# perfboard.net
KiCad netlist of a schematic drawn in EAGLE
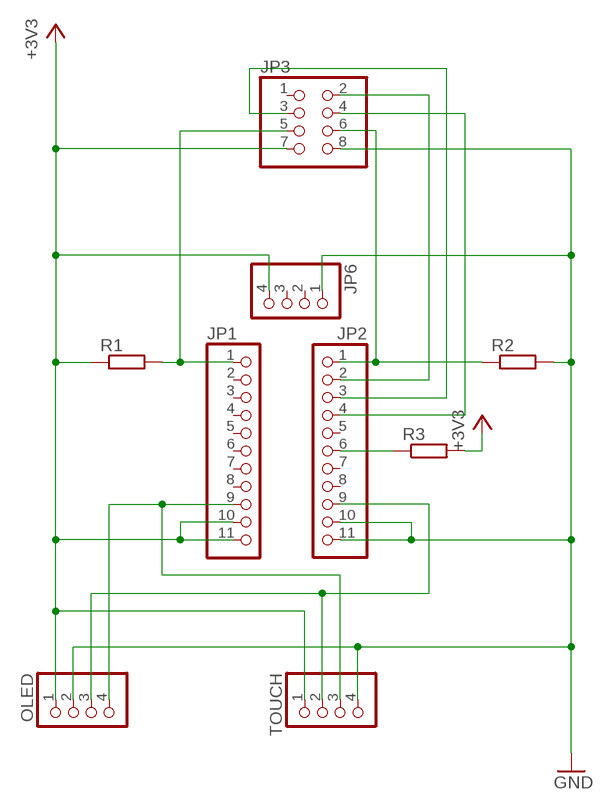
[diagram p0: schematic, sheet 1]

(export (version "E")
  (design (tool "Eeschema 10.0.6"))
  (components
    (comp (ref "JP1")
      (value "PINHD-1X11")
      (footprint "eagle-import:1X11")
      (libsource (lib "eagle-import") (part "PINHD-1X11"))
    )
    (comp (ref "JP2")
      (value "PINHD-1X11")
      (footprint "eagle-import:1X11")
      (libsource (lib "eagle-import") (part "PINHD-1X11"))
    )
    (comp (ref "JP3")
      (value "PINHD-2X4")
      (footprint "eagle-import:2X04")
      (libsource (lib "eagle-import") (part "PINHD-2X4"))
    )
    (comp (ref "JP6")
      (value "PINHD-1X4")
      (footprint "eagle-import:1X04")
      (libsource (lib "eagle-import") (part "PINHD-1X4"))
    )
    (comp (ref "OLED")
      (value "PINHD-1X4")
      (footprint "eagle-import:1X04")
      (libsource (lib "eagle-import") (part "PINHD-1X4"))
    )
    (comp (ref "R1")
      (value "R-EU_0207/7")
      (footprint "eagle-import:0207_7")
      (libsource (lib "eagle-import") (part "R-EU_0207/7"))
    )
    (comp (ref "R2")
      (value "R-EU_0207/7")
      (footprint "eagle-import:0207_7")
      (libsource (lib "eagle-import") (part "R-EU_0207/7"))
    )
    (comp (ref "R3")
      (value "R-EU_0207/7")
      (footprint "eagle-import:0207_7")
      (libsource (lib "eagle-import") (part "R-EU_0207/7"))
    )
    (comp (ref "TOUCH")
      (value "PINHD-1X4")
      (footprint "eagle-import:1X04")
      (libsource (lib "eagle-import") (part "PINHD-1X4"))
    )
  )
  (nets
    (net (code "1") (name "+3V3") (class "Default")
      (node (ref "JP1") (pin "10") (pinfunction "10_10") (pintype "passive"))
      (node (ref "JP1") (pin "11") (pinfunction "11_11") (pintype "passive"))
      (node (ref "JP3") (pin "7") (pinfunction "7_7") (pintype "passive"))
      (node (ref "JP6") (pin "4") (pinfunction "4_4") (pintype "passive"))
      (node (ref "OLED") (pin "1") (pinfunction "1_1") (pintype "passive"))
      (node (ref "R1") (pin "1") (pinfunction "1_1") (pintype "passive"))
      (node (ref "R3") (pin "2") (pinfunction "2_2") (pintype "passive"))
      (node (ref "TOUCH") (pin "1") (pinfunction "1_1") (pintype "passive"))
    )
    (net (code "2") (name "GND") (class "Default")
      (node (ref "JP2") (pin "10") (pinfunction "10_10") (pintype "passive"))
      (node (ref "JP2") (pin "11") (pinfunction "11_11") (pintype "passive"))
      (node (ref "JP3") (pin "8") (pinfunction "8_8") (pintype "passive"))
      (node (ref "JP6") (pin "1") (pinfunction "1_1") (pintype "passive"))
      (node (ref "OLED") (pin "2") (pinfunction "2_2") (pintype "passive"))
      (node (ref "R2") (pin "2") (pinfunction "2_2") (pintype "passive"))
      (node (ref "TOUCH") (pin "4") (pinfunction "4_4") (pintype "passive"))
    )
    (net (code "3") (name "Net-(JP1-Pad1)") (class "Default")
      (node (ref "JP1") (pin "1") (pinfunction "1_1") (pintype "passive"))
      (node (ref "JP3") (pin "5") (pinfunction "5_5") (pintype "passive"))
      (node (ref "R1") (pin "2") (pinfunction "2_2") (pintype "passive"))
    )
    (net (code "4") (name "Net-(JP1-Pad9)") (class "Default")
      (node (ref "JP1") (pin "9") (pinfunction "9_9") (pintype "passive"))
      (node (ref "OLED") (pin "4") (pinfunction "4_4") (pintype "passive"))
      (node (ref "TOUCH") (pin "3") (pinfunction "3_3") (pintype "passive"))
    )
    (net (code "5") (name "Net-(JP2-Pad1)") (class "Default")
      (node (ref "JP2") (pin "1") (pinfunction "1_1") (pintype "passive"))
      (node (ref "JP3") (pin "6") (pinfunction "6_6") (pintype "passive"))
      (node (ref "R2") (pin "1") (pinfunction "1_1") (pintype "passive"))
    )
    (net (code "6") (name "Net-(JP2-Pad2)") (class "Default")
      (node (ref "JP2") (pin "2") (pinfunction "2_2") (pintype "passive"))
      (node (ref "JP3") (pin "2") (pinfunction "2_2") (pintype "passive"))
    )
    (net (code "7") (name "Net-(JP2-Pad3)") (class "Default")
      (node (ref "JP2") (pin "3") (pinfunction "3_3") (pintype "passive"))
      (node (ref "JP3") (pin "3") (pinfunction "3_3") (pintype "passive"))
    )
    (net (code "8") (name "Net-(JP2-Pad4)") (class "Default")
      (node (ref "JP2") (pin "4") (pinfunction "4_4") (pintype "passive"))
      (node (ref "JP3") (pin "4") (pinfunction "4_4") (pintype "passive"))
    )
    (net (code "9") (name "Net-(JP2-Pad6)") (class "Default")
      (node (ref "JP2") (pin "6") (pinfunction "6_6") (pintype "passive"))
      (node (ref "R3") (pin "1") (pinfunction "1_1") (pintype "passive"))
    )
    (net (code "10") (name "Net-(JP2-Pad9)") (class "Default")
      (node (ref "JP2") (pin "9") (pinfunction "9_9") (pintype "passive"))
      (node (ref "OLED") (pin "3") (pinfunction "3_3") (pintype "passive"))
      (node (ref "TOUCH") (pin "2") (pinfunction "2_2") (pintype "passive"))
    )
    (net (code "11") (name "unconnected-(JP1-Pad2)") (class "Default")
      (node (ref "JP1") (pin "2") (pinfunction "2_2") (pintype "passive"))
    )
    (net (code "12") (name "unconnected-(JP1-Pad3)") (class "Default")
      (node (ref "JP1") (pin "3") (pinfunction "3_3") (pintype "passive"))
    )
    (net (code "13") (name "unconnected-(JP1-Pad4)") (class "Default")
      (node (ref "JP1") (pin "4") (pinfunction "4_4") (pintype "passive"))
    )
    (net (code "14") (name "unconnected-(JP1-Pad5)") (class "Default")
      (node (ref "JP1") (pin "5") (pinfunction "5_5") (pintype "passive"))
    )
    (net (code "15") (name "unconnected-(JP1-Pad6)") (class "Default")
      (node (ref "JP1") (pin "6") (pinfunction "6_6") (pintype "passive"))
    )
    (net (code "16") (name "unconnected-(JP1-Pad7)") (class "Default")
      (node (ref "JP1") (pin "7") (pinfunction "7_7") (pintype "passive"))
    )
    (net (code "17") (name "unconnected-(JP1-Pad8)") (class "Default")
      (node (ref "JP1") (pin "8") (pinfunction "8_8") (pintype "passive"))
    )
    (net (code "18") (name "unconnected-(JP2-Pad5)") (class "Default")
      (node (ref "JP2") (pin "5") (pinfunction "5_5") (pintype "passive"))
    )
    (net (code "19") (name "unconnected-(JP2-Pad7)") (class "Default")
      (node (ref "JP2") (pin "7") (pinfunction "7_7") (pintype "passive"))
    )
    (net (code "20") (name "unconnected-(JP2-Pad8)") (class "Default")
      (node (ref "JP2") (pin "8") (pinfunction "8_8") (pintype "passive"))
    )
    (net (code "21") (name "unconnected-(JP3-Pad1)") (class "Default")
      (node (ref "JP3") (pin "1") (pinfunction "1_1") (pintype "passive"))
    )
    (net (code "22") (name "unconnected-(JP6-Pad2)") (class "Default")
      (node (ref "JP6") (pin "2") (pinfunction "2_2") (pintype "passive"))
    )
    (net (code "23") (name "unconnected-(JP6-Pad3)") (class "Default")
      (node (ref "JP6") (pin "3") (pinfunction "3_3") (pintype "passive"))
    )
  )
)
